# PCB-MicroSmartE.net
KiCad netlist of a schematic drawn in EAGLE
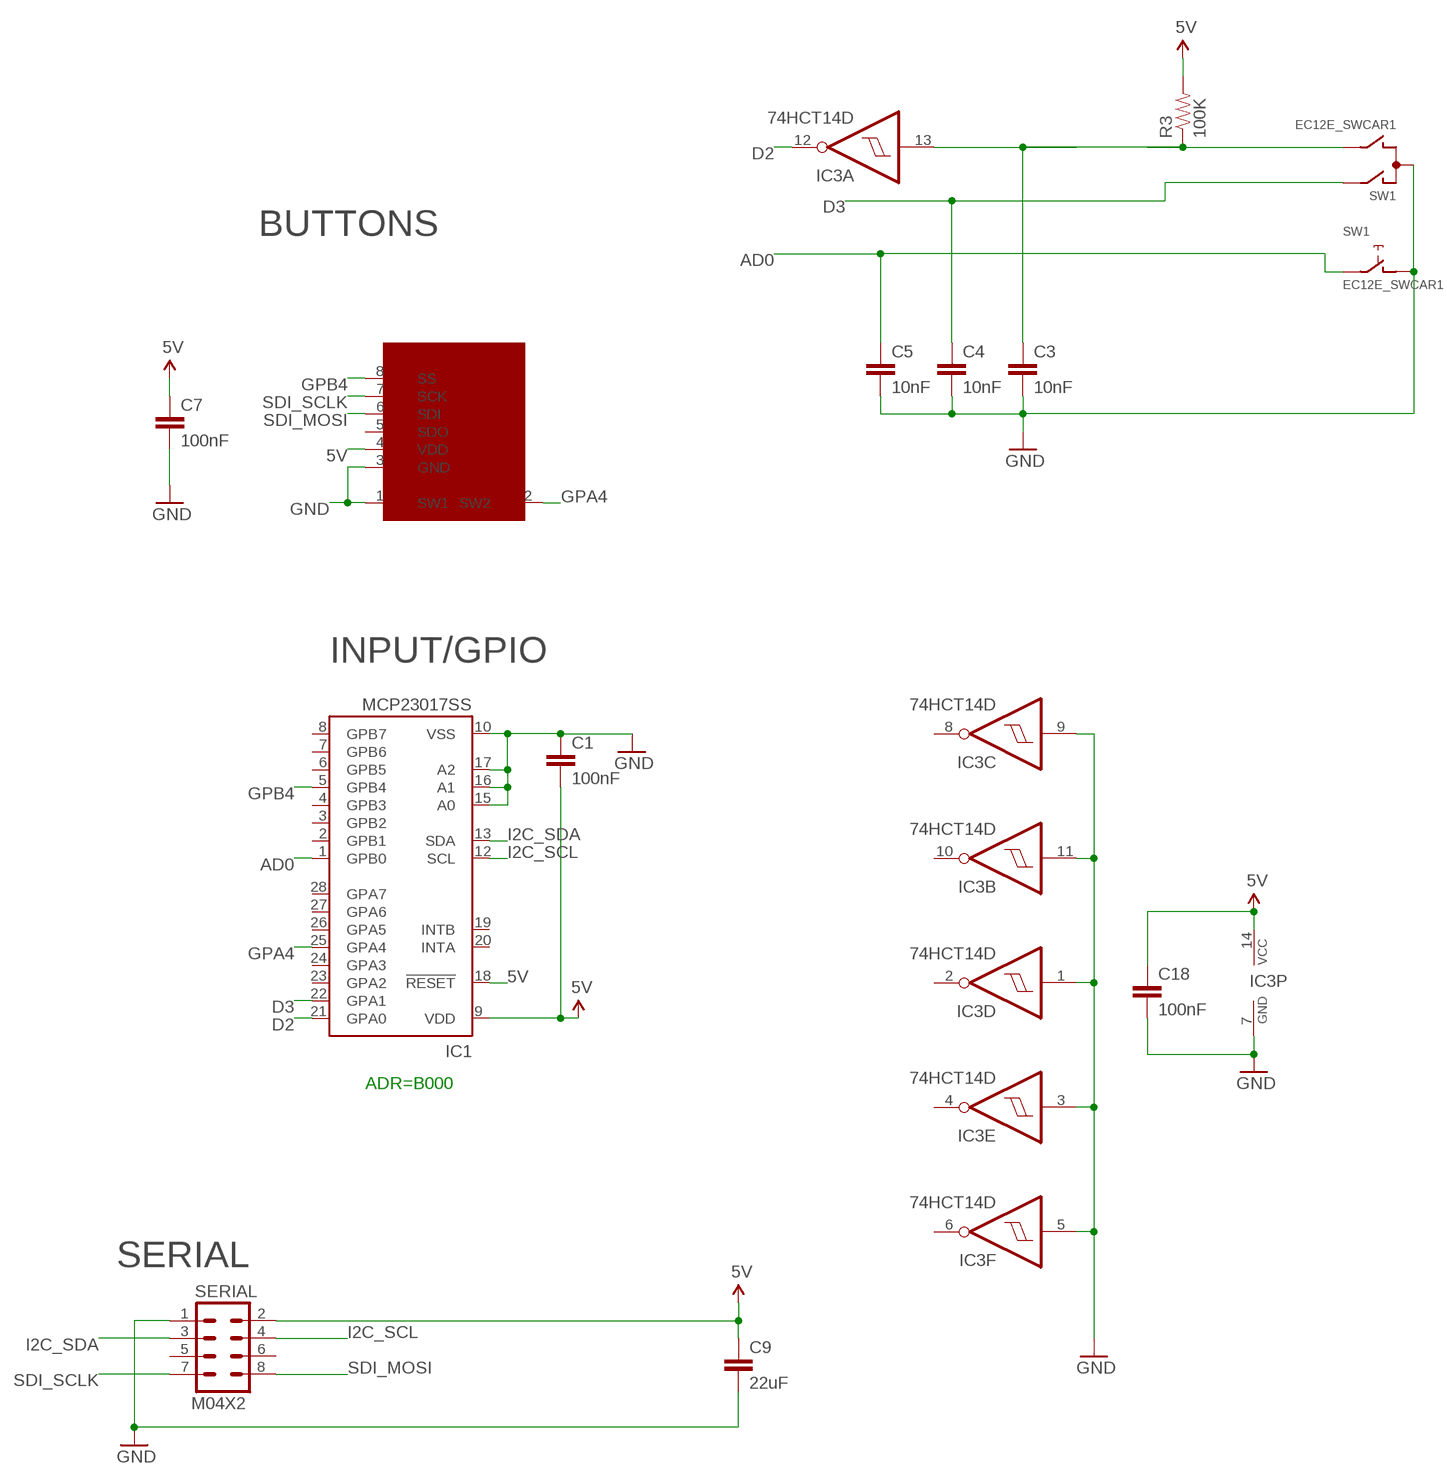
[diagram p0: schematic, sheet 1]

(export (version "E")
  (design (tool "Eeschema 10.0.6"))
  (components
    (comp (ref "C1")
      (value "100nF")
      (footprint "eagle-import:0603-CAP")
      (libsource (lib "eagle-import") (part "CAP0603-CAP"))
    )
    (comp (ref "C3")
      (value "10nF")
      (footprint "eagle-import:0603-CAP")
      (libsource (lib "eagle-import") (part "CAP0603-CAP"))
    )
    (comp (ref "C4")
      (value "10nF")
      (footprint "eagle-import:0603-CAP")
      (libsource (lib "eagle-import") (part "CAP0603-CAP"))
    )
    (comp (ref "C5")
      (value "10nF")
      (footprint "eagle-import:0603-CAP")
      (libsource (lib "eagle-import") (part "CAP0603-CAP"))
    )
    (comp (ref "C7")
      (value "100nF")
      (footprint "eagle-import:0603-CAP")
      (libsource (lib "eagle-import") (part "CAP0603-CAP"))
    )
    (comp (ref "C9")
      (value "22uF")
      (footprint "eagle-import:0805")
      (libsource (lib "eagle-import") (part "CAP0805"))
    )
    (comp (ref "C18")
      (value "100nF")
      (footprint "eagle-import:0603-CAP")
      (libsource (lib "eagle-import") (part "CAP0603-CAP"))
    )
    (comp (ref "IC1")
      (value "MCP23017SS")
      (footprint "eagle-import:SSOP28")
      (fields
        (field (name "MF") "MICROCHIP")
        (field (name "MPN") "MCP23017-E/SS")
        (field (name "MPN_1") "MCP23017-E/SS")
        (field (name "OC_FARNELL") "1467674")
        (field (name "OC_NEWARK") "31K2960")
      )
      (libsource (lib "eagle-import") (part "MCP23017SS"))
    )
    (comp (ref "IC3")
      (value "74HCT14D")
      (footprint "eagle-import:SO14")
      (libsource (lib "eagle-import") (part "7414DHCT"))
    )
    (comp (ref "R3")
      (value "100K")
      (footprint "eagle-import:0603-RES")
      (libsource (lib "eagle-import") (part "RESISTOR0603-RES"))
    )
    (comp (ref "SERIAL")
      (value "M04X2")
      (footprint "eagle-import:2X4")
      (libsource (lib "eagle-import") (part "M04X2"))
    )
    (comp (ref "SSW1")
      (value "SMART_SWITCHSMART_SWITCH_8PIN")
      (footprint "eagle-import:SMART_SWITCH")
      (libsource (lib "eagle-import") (part "SMART_SWITCHSMART_SWITCH_8PIN"))
    )
    (comp (ref "SW1")
      (value "EC12E_SWCAR1")
      (footprint "eagle-import:ALPS_EC12E_SW-CAR1")
      (libsource (lib "eagle-import") (part "EC12E_SWCAR1"))
    )
  )
  (nets
    (net (code "1") (name "/AD0") (class "Default")
      (node (ref "C5") (pin "1") (pinfunction "1_1") (pintype "passive"))
      (node (ref "IC1") (pin "1") (pinfunction "GPB0_1") (pintype "bidirectional"))
      (node (ref "SW1") (pin "E") (pinfunction "2_E") (pintype "passive"))
    )
    (net (code "2") (name "/D2") (class "Default")
      (node (ref "IC1") (pin "21") (pinfunction "GPA0_21") (pintype "bidirectional"))
      (node (ref "IC3") (pin "12") (pinfunction "O_12") (pintype "output"))
    )
    (net (code "3") (name "/D3") (class "Default")
      (node (ref "C4") (pin "1") (pinfunction "1_1") (pintype "passive"))
      (node (ref "IC1") (pin "22") (pinfunction "GPA1_22") (pintype "bidirectional"))
      (node (ref "SW1") (pin "A") (pinfunction "A_A") (pintype "passive"))
    )
    (net (code "4") (name "/GPA4") (class "Default")
      (node (ref "IC1") (pin "25") (pinfunction "GPA4_25") (pintype "bidirectional"))
      (node (ref "SSW1") (pin "2") (pinfunction "SW2_2") (pintype "bidirectional"))
    )
    (net (code "5") (name "/GPB4") (class "Default")
      (node (ref "IC1") (pin "5") (pinfunction "GPB4_5") (pintype "bidirectional"))
      (node (ref "SSW1") (pin "8") (pinfunction "SS_8") (pintype "bidirectional"))
    )
    (net (code "6") (name "/I2C_SCL") (class "Default")
      (node (ref "IC1") (pin "12") (pinfunction "SCL_12") (pintype "input"))
      (node (ref "SERIAL") (pin "4") (pinfunction "4_4") (pintype "passive"))
    )
    (net (code "7") (name "/I2C_SDA") (class "Default")
      (node (ref "IC1") (pin "13") (pinfunction "SDA_13") (pintype "bidirectional"))
      (node (ref "SERIAL") (pin "3") (pinfunction "3_3") (pintype "passive"))
    )
    (net (code "8") (name "/SDI_MOSI") (class "Default")
      (node (ref "SERIAL") (pin "8") (pinfunction "8_8") (pintype "passive"))
      (node (ref "SSW1") (pin "6") (pinfunction "SDI_6") (pintype "bidirectional"))
    )
    (net (code "9") (name "/SDI_SCLK") (class "Default")
      (node (ref "SERIAL") (pin "7") (pinfunction "7_7") (pintype "passive"))
      (node (ref "SSW1") (pin "7") (pinfunction "SCK_7") (pintype "bidirectional"))
    )
    (net (code "10") (name "5V") (class "Default")
      (node (ref "C1") (pin "2") (pinfunction "2_2") (pintype "passive"))
      (node (ref "C18") (pin "1") (pinfunction "1_1") (pintype "passive"))
      (node (ref "C7") (pin "1") (pinfunction "1_1") (pintype "passive"))
      (node (ref "C9") (pin "1") (pinfunction "1_1") (pintype "passive"))
      (node (ref "IC1") (pin "18") (pinfunction "~{RESET}_18") (pintype "input"))
      (node (ref "IC1") (pin "9") (pinfunction "VDD_9") (pintype "power_in"))
      (node (ref "IC3") (pin "14") (pinfunction "VCC_14") (pintype "power_in"))
      (node (ref "R3") (pin "2") (pinfunction "2_2") (pintype "passive"))
      (node (ref "SERIAL") (pin "2") (pinfunction "2_2") (pintype "passive"))
      (node (ref "SSW1") (pin "4") (pinfunction "VDD_4") (pintype "bidirectional"))
    )
    (net (code "11") (name "GND") (class "Default")
      (node (ref "C1") (pin "1") (pinfunction "1_1") (pintype "passive"))
      (node (ref "C18") (pin "2") (pinfunction "2_2") (pintype "passive"))
      (node (ref "C3") (pin "2") (pinfunction "2_2") (pintype "passive"))
      (node (ref "C4") (pin "2") (pinfunction "2_2") (pintype "passive"))
      (node (ref "C5") (pin "2") (pinfunction "2_2") (pintype "passive"))
      (node (ref "C7") (pin "2") (pinfunction "2_2") (pintype "passive"))
      (node (ref "C9") (pin "2") (pinfunction "2_2") (pintype "passive"))
      (node (ref "IC1") (pin "10") (pinfunction "VSS_10") (pintype "power_in"))
      (node (ref "IC1") (pin "15") (pinfunction "A0_15") (pintype "input"))
      (node (ref "IC1") (pin "16") (pinfunction "A1_16") (pintype "input"))
      (node (ref "IC1") (pin "17") (pinfunction "A2_17") (pintype "input"))
      (node (ref "IC3") (pin "1") (pinfunction "I_1") (pintype "input"))
      (node (ref "IC3") (pin "11") (pinfunction "I_11") (pintype "input"))
      (node (ref "IC3") (pin "3") (pinfunction "I_3") (pintype "input"))
      (node (ref "IC3") (pin "5") (pinfunction "I_5") (pintype "input"))
      (node (ref "IC3") (pin "7") (pinfunction "GND_7") (pintype "power_in"))
      (node (ref "IC3") (pin "9") (pinfunction "I_9") (pintype "input"))
      (node (ref "SERIAL") (pin "1") (pinfunction "1_1") (pintype "passive"))
      (node (ref "SSW1") (pin "1") (pinfunction "SW1_1") (pintype "bidirectional"))
      (node (ref "SSW1") (pin "3") (pinfunction "GND_3") (pintype "bidirectional"))
      (node (ref "SW1") (pin "C") (pinfunction "C_C") (pintype "passive"))
      (node (ref "SW1") (pin "D") (pinfunction "1_D") (pintype "passive"))
    )
    (net (code "12") (name "Net-(IC3A-I)") (class "Default")
      (node (ref "C3") (pin "1") (pinfunction "1_1") (pintype "passive"))
      (node (ref "IC3") (pin "13") (pinfunction "I_13") (pintype "input"))
      (node (ref "R3") (pin "1") (pinfunction "1_1") (pintype "passive"))
      (node (ref "SW1") (pin "B") (pinfunction "B_B") (pintype "passive"))
    )
    (net (code "13") (name "unconnected-(IC1-GPA2-Pad23)") (class "Default")
      (node (ref "IC1") (pin "23") (pinfunction "GPA2_23") (pintype "bidirectional"))
    )
    (net (code "14") (name "unconnected-(IC1-GPA3-Pad24)") (class "Default")
      (node (ref "IC1") (pin "24") (pinfunction "GPA3_24") (pintype "bidirectional"))
    )
    (net (code "15") (name "unconnected-(IC1-GPA5-Pad26)") (class "Default")
      (node (ref "IC1") (pin "26") (pinfunction "GPA5_26") (pintype "bidirectional"))
    )
    (net (code "16") (name "unconnected-(IC1-GPA6-Pad27)") (class "Default")
      (node (ref "IC1") (pin "27") (pinfunction "GPA6_27") (pintype "bidirectional"))
    )
    (net (code "17") (name "unconnected-(IC1-GPA7-Pad28)") (class "Default")
      (node (ref "IC1") (pin "28") (pinfunction "GPA7_28") (pintype "bidirectional"))
    )
    (net (code "18") (name "unconnected-(IC1-GPB1-Pad2)") (class "Default")
      (node (ref "IC1") (pin "2") (pinfunction "GPB1_2") (pintype "bidirectional"))
    )
    (net (code "19") (name "unconnected-(IC1-GPB2-Pad3)") (class "Default")
      (node (ref "IC1") (pin "3") (pinfunction "GPB2_3") (pintype "bidirectional"))
    )
    (net (code "20") (name "unconnected-(IC1-GPB3-Pad4)") (class "Default")
      (node (ref "IC1") (pin "4") (pinfunction "GPB3_4") (pintype "bidirectional"))
    )
    (net (code "21") (name "unconnected-(IC1-GPB5-Pad6)") (class "Default")
      (node (ref "IC1") (pin "6") (pinfunction "GPB5_6") (pintype "bidirectional"))
    )
    (net (code "22") (name "unconnected-(IC1-GPB6-Pad7)") (class "Default")
      (node (ref "IC1") (pin "7") (pinfunction "GPB6_7") (pintype "bidirectional"))
    )
    (net (code "23") (name "unconnected-(IC1-GPB7-Pad8)") (class "Default")
      (node (ref "IC1") (pin "8") (pinfunction "GPB7_8") (pintype "bidirectional"))
    )
    (net (code "24") (name "unconnected-(IC1-INTA-Pad20)") (class "Default")
      (node (ref "IC1") (pin "20") (pinfunction "INTA_20") (pintype "output"))
    )
    (net (code "25") (name "unconnected-(IC1-INTB-Pad19)") (class "Default")
      (node (ref "IC1") (pin "19") (pinfunction "INTB_19") (pintype "output"))
    )
    (net (code "26") (name "unconnected-(IC3B-O-Pad10)") (class "Default")
      (node (ref "IC3") (pin "10") (pinfunction "O_10") (pintype "output"))
    )
    (net (code "27") (name "unconnected-(IC3C-O-Pad8)") (class "Default")
      (node (ref "IC3") (pin "8") (pinfunction "O_8") (pintype "output"))
    )
    (net (code "28") (name "unconnected-(IC3D-O-Pad2)") (class "Default")
      (node (ref "IC3") (pin "2") (pinfunction "O_2") (pintype "output"))
    )
    (net (code "29") (name "unconnected-(IC3E-O-Pad4)") (class "Default")
      (node (ref "IC3") (pin "4") (pinfunction "O_4") (pintype "output"))
    )
    (net (code "30") (name "unconnected-(IC3F-O-Pad6)") (class "Default")
      (node (ref "IC3") (pin "6") (pinfunction "O_6") (pintype "output"))
    )
    (net (code "31") (name "unconnected-(SERIAL-Pad5)") (class "Default")
      (node (ref "SERIAL") (pin "5") (pinfunction "5_5") (pintype "passive"))
    )
    (net (code "32") (name "unconnected-(SERIAL-Pad6)") (class "Default")
      (node (ref "SERIAL") (pin "6") (pinfunction "6_6") (pintype "passive"))
    )
    (net (code "33") (name "unconnected-(SSW1-SDO-Pad5)") (class "Default")
      (node (ref "SSW1") (pin "5") (pinfunction "SDO_5") (pintype "bidirectional"))
    )
  )
)
